# Power.net
KiCad netlist of a schematic drawn in Altium Designer
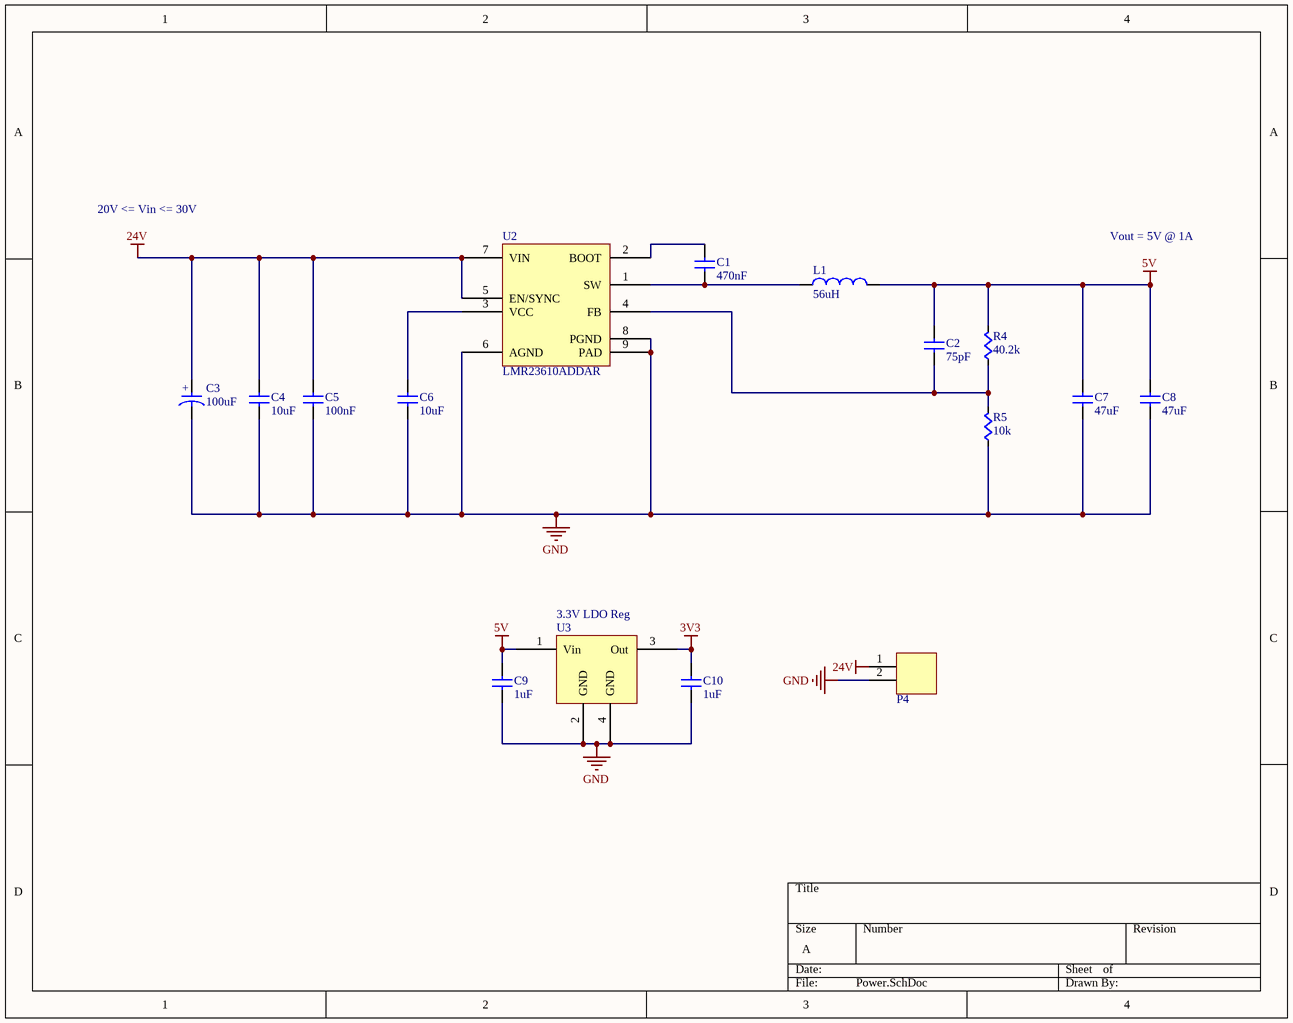
[diagram p0: Power.SchDoc]

(export (version "E")
  (design (tool "Eeschema 10.0.6"))
  (components
    (comp (ref "C1")
      (value "470nF")
      (footprint "CAPC0603")
      (fields (field (name "Comment") "Cap"))
      (libsource (lib "Passives") (part "Cap"))
    )
    (comp (ref "C2")
      (value "75pF")
      (footprint "CAPC0603")
      (fields (field (name "Comment") "Cap"))
      (libsource (lib "Passives") (part "Cap"))
    )
    (comp (ref "C3")
      (value "100uF")
      (footprint "EEHZA1H101P")
      (description "CAP ALUM POLY HYB 100UF 50V SMD")
      (fields (field (name "VOLTAGE") "50V") (field (name "TOLERANCE") "20%"))
      (libsource (lib "SubjuGator8") (part "EEHZA1H101P"))
    )
    (comp (ref "C4")
      (value "10uF")
      (footprint "CAP1210")
      (fields (field (name "Comment") "Cap"))
      (libsource (lib "Passives") (part "Cap"))
    )
    (comp (ref "C5")
      (value "100nF")
      (footprint "CAPC0603")
      (fields (field (name "Comment") "Cap"))
      (libsource (lib "Passives") (part "Cap"))
    )
    (comp (ref "C6")
      (value "10uF")
      (footprint "CAPC0603")
      (fields (field (name "Comment") "Cap"))
      (libsource (lib "Passives") (part "Cap"))
    )
    (comp (ref "C7")
      (value "47uF")
      (footprint "CAP1210")
      (fields (field (name "Comment") "Cap"))
      (libsource (lib "SubjuGator8") (part "Cap"))
    )
    (comp (ref "C8")
      (value "47uF")
      (footprint "CAP1210")
      (fields (field (name "Comment") "Cap"))
      (libsource (lib "SubjuGator8") (part "Cap"))
    )
    (comp (ref "C9")
      (value "1uF")
      (footprint "CAPC0603")
      (fields (field (name "Comment") "Cap"))
      (libsource (lib "SubjuGator8") (part "Cap"))
    )
    (comp (ref "C10")
      (value "1uF")
      (footprint "CAPC0603")
      (fields (field (name "Comment") "Cap"))
      (libsource (lib "SubjuGator8") (part "Cap"))
    )
    (comp (ref "L1")
      (value "56uH")
      (footprint "MSS1048-563MLB")
      (description "FIXED IND 56UH 1.7A 126 MOHM")
      (fields (field (name "Comment") "MSS1048-563MLB"))
      (libsource (lib "SubjuGator8") (part "MSS1048-563MLB"))
    )
    (comp (ref "P4")
      (value "2-pin Vert Sherlock")
      (footprint "MOLEX-HDR-1X2-SHERLOCK-VERT")
      (libsource (lib "Connectors") (part "MOLEX-HDR-1x2-SHERLOCK_VERT"))
    )
    (comp (ref "R4")
      (value "40.2k")
      (footprint "RES0603")
      (fields (field (name "Comment") "Res"))
      (libsource (lib "SubjuGator8") (part "Res"))
    )
    (comp (ref "R5")
      (value "10k")
      (footprint "RES0603")
      (fields (field (name "Comment") "Res"))
      (libsource (lib "SubjuGator8") (part "Res"))
    )
    (comp (ref "U2")
      (value "LMR23610ADDAR")
      (footprint "LMR23610ADDAR")
      (description "IC REG BUCK ADJ 1A SYNC 8SOPWRPD")
      (libsource (lib "SubjuGator8") (part "LMR23610ADDAR"))
    )
    (comp (ref "U3")
      (value "3.3V LDO Reg")
      (footprint "SOT23-4n")
      (description "IC REG LDO 3.3V 1A SOT223")
      (libsource (lib "SubjuGator8") (part "LM3940IMPX-3.3"))
    )
  )
  (nets
    (net (code "1") (name "3V3") (class "Default")
      (node (ref "C10") (pin "1") (pinfunction "A_1") (pintype "passive"))
      (node (ref "U3") (pin "3") (pinfunction "Out_3") (pintype "passive"))
    )
    (net (code "2") (name "5V") (class "Default")
      (node (ref "C2") (pin "1") (pinfunction "A_1") (pintype "passive"))
      (node (ref "C7") (pin "1") (pinfunction "A_1") (pintype "passive"))
      (node (ref "C8") (pin "1") (pinfunction "A_1") (pintype "passive"))
      (node (ref "C9") (pin "1") (pinfunction "A_1") (pintype "passive"))
      (node (ref "L1") (pin "2") (pinfunction "2_2") (pintype "passive"))
      (node (ref "R4") (pin "1") (pinfunction "A_1") (pintype "passive"))
      (node (ref "U3") (pin "1") (pinfunction "Vin_1") (pintype "passive"))
    )
    (net (code "3") (name "24V") (class "Default")
      (node (ref "C3") (pin "1") (pinfunction "1_1") (pintype "passive"))
      (node (ref "C4") (pin "1") (pinfunction "A_1") (pintype "passive"))
      (node (ref "C5") (pin "1") (pinfunction "A_1") (pintype "passive"))
      (node (ref "P4") (pin "1") (pinfunction "1_1") (pintype "passive"))
      (node (ref "U2") (pin "5") (pinfunction "EN/SYNC_5") (pintype "passive"))
      (node (ref "U2") (pin "7") (pinfunction "VIN_7") (pintype "passive"))
    )
    (net (code "4") (name "GND") (class "Default")
      (node (ref "C10") (pin "2") (pinfunction "B_2") (pintype "passive"))
      (node (ref "C3") (pin "2") (pinfunction "2_2") (pintype "passive"))
      (node (ref "C4") (pin "2") (pinfunction "B_2") (pintype "passive"))
      (node (ref "C5") (pin "2") (pinfunction "B_2") (pintype "passive"))
      (node (ref "C6") (pin "2") (pinfunction "B_2") (pintype "passive"))
      (node (ref "C7") (pin "2") (pinfunction "B_2") (pintype "passive"))
      (node (ref "C8") (pin "2") (pinfunction "B_2") (pintype "passive"))
      (node (ref "C9") (pin "2") (pinfunction "B_2") (pintype "passive"))
      (node (ref "P4") (pin "2") (pinfunction "2_2") (pintype "passive"))
      (node (ref "R5") (pin "2") (pinfunction "B_2") (pintype "passive"))
      (node (ref "U2") (pin "6") (pinfunction "AGND_6") (pintype "passive"))
      (node (ref "U2") (pin "8") (pinfunction "PGND_8") (pintype "passive"))
      (node (ref "U2") (pin "9") (pinfunction "PAD_9") (pintype "passive"))
      (node (ref "U3") (pin "2") (pinfunction "GND_2") (pintype "passive"))
      (node (ref "U3") (pin "4") (pinfunction "GND_4") (pintype "passive"))
    )
    (net (code "5") (name "Net-(C1-A)") (class "Default")
      (node (ref "C1") (pin "1") (pinfunction "A_1") (pintype "passive"))
      (node (ref "U2") (pin "2") (pinfunction "BOOT_2") (pintype "passive"))
    )
    (net (code "6") (name "Net-(C1-B)") (class "Default")
      (node (ref "C1") (pin "2") (pinfunction "B_2") (pintype "passive"))
      (node (ref "L1") (pin "1") (pinfunction "1_1") (pintype "passive"))
      (node (ref "U2") (pin "1") (pinfunction "SW_1") (pintype "passive"))
    )
    (net (code "7") (name "Net-(C2-B)") (class "Default")
      (node (ref "C2") (pin "2") (pinfunction "B_2") (pintype "passive"))
      (node (ref "R4") (pin "2") (pinfunction "B_2") (pintype "passive"))
      (node (ref "R5") (pin "1") (pinfunction "A_1") (pintype "passive"))
      (node (ref "U2") (pin "4") (pinfunction "FB_4") (pintype "passive"))
    )
    (net (code "8") (name "Net-(C6-A)") (class "Default")
      (node (ref "C6") (pin "1") (pinfunction "A_1") (pintype "passive"))
      (node (ref "U2") (pin "3") (pinfunction "VCC_3") (pintype "passive"))
    )
  )
)
